# STUSB4500.net
KiCad netlist of a schematic drawn in EAGLE
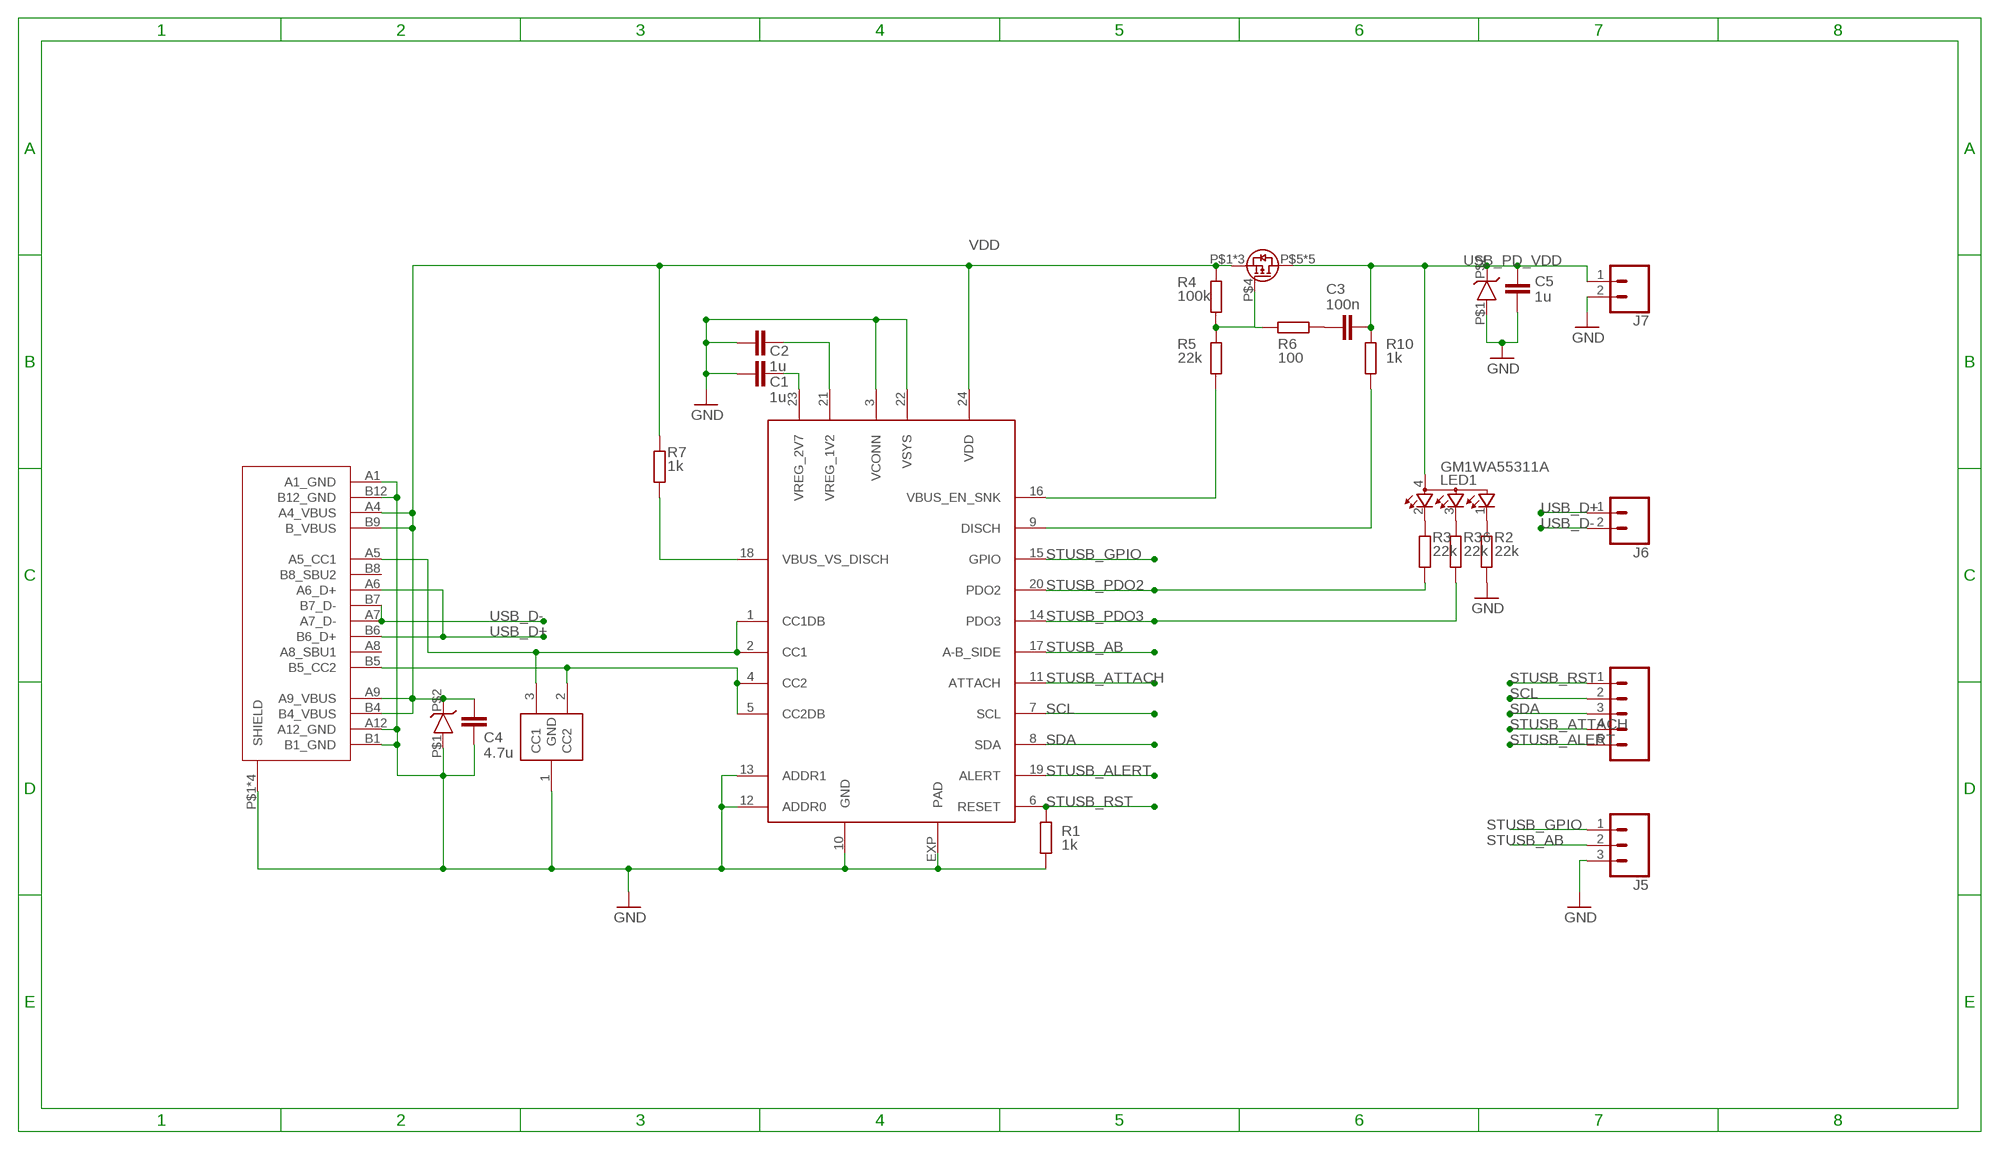
[diagram p0: schematic, sheet 1]

(export (version "E")
  (design (tool "Eeschema 10.0.6"))
  (components
    (comp (ref "C1")
      (value "1u")
      (footprint "eagle-import:C0402")
      (libsource (lib "eagle-import") (part "C-EUC0402"))
    )
    (comp (ref "C2")
      (value "1u")
      (footprint "eagle-import:C0402")
      (libsource (lib "eagle-import") (part "C-EUC0402"))
    )
    (comp (ref "C3")
      (value "100n")
      (footprint "eagle-import:C0402")
      (libsource (lib "eagle-import") (part "C-EUC0402"))
    )
    (comp (ref "C4")
      (value "4.7u")
      (footprint "eagle-import:C1206")
      (libsource (lib "eagle-import") (part "C-EUC1206"))
    )
    (comp (ref "C5")
      (value "1u")
      (footprint "eagle-import:C1206")
      (libsource (lib "eagle-import") (part "C-EUC1206"))
    )
    (comp (ref "ESDA25W")
      (value "ESDA25WSOT323")
      (footprint "eagle-import:SOT323")
      (libsource (lib "eagle-import") (part "ESDA25WSOT323"))
    )
    (comp (ref "J5")
      (value "CONN_031.27")
      (footprint "eagle-import:1X03_1.27MM")
      (libsource (lib "eagle-import") (part "CONN_031.27"))
    )
    (comp (ref "J6")
      (value "CONN_021.27")
      (footprint "eagle-import:1X02_1.27MM")
      (libsource (lib "eagle-import") (part "CONN_021.27"))
    )
    (comp (ref "J7")
      (value "CONN_02LOCK")
      (footprint "eagle-import:1X02_LOCK")
      (libsource (lib "eagle-import") (part "CONN_02LOCK"))
    )
    (comp (ref "J8")
      (value "CONN_051.27MM")
      (footprint "eagle-import:1X05_1.27MM")
      (libsource (lib "eagle-import") (part "CONN_051.27MM"))
    )
    (comp (ref "LED1")
      (value "GM1WA55311A")
      (footprint "eagle-import:GM1WA55311A")
      (libsource (lib "eagle-import") (part "GM1WA55311A"))
    )
    (comp (ref "R1")
      (value "1k")
      (footprint "eagle-import:R0402")
      (libsource (lib "eagle-import") (part "R-EU_R0402"))
    )
    (comp (ref "R2")
      (value "22k")
      (footprint "eagle-import:R0402")
      (libsource (lib "eagle-import") (part "R-EU_R0402"))
    )
    (comp (ref "R3")
      (value "22k")
      (footprint "eagle-import:R0402")
      (libsource (lib "eagle-import") (part "R-EU_R0402"))
    )
    (comp (ref "R4")
      (value "100k")
      (footprint "eagle-import:R0402")
      (libsource (lib "eagle-import") (part "R-EU_R0402"))
    )
    (comp (ref "R5")
      (value "22k")
      (footprint "eagle-import:R0402")
      (libsource (lib "eagle-import") (part "R-EU_R0402"))
    )
    (comp (ref "R6")
      (value "100")
      (footprint "eagle-import:R0402")
      (libsource (lib "eagle-import") (part "R-EU_R0402"))
    )
    (comp (ref "R7")
      (value "1k")
      (footprint "eagle-import:R0402")
      (libsource (lib "eagle-import") (part "R-EU_R0402"))
    )
    (comp (ref "R10")
      (value "1k")
      (footprint "eagle-import:R0402")
      (libsource (lib "eagle-import") (part "R-EU_R0402"))
    )
    (comp (ref "R36")
      (value "22k")
      (footprint "eagle-import:R0402")
      (libsource (lib "eagle-import") (part "R-EU_R0402"))
    )
    (comp (ref "U$1")
      (value "STUSB4500QFN24_4X4")
      (footprint "eagle-import:QFN24-4X4")
      (libsource (lib "eagle-import") (part "STUSB4500QFN24_4X4"))
    )
    (comp (ref "U$2")
      (value "USB-C")
      (footprint "eagle-import:USB-C_16P")
      (libsource (lib "eagle-import") (part "USB-C"))
    )
    (comp (ref "U$4")
      (value "ESDA25P35")
      (footprint "eagle-import:1610")
      (libsource (lib "eagle-import") (part "ESDA25P35"))
    )
    (comp (ref "U$5")
      (value "ESDA25P35")
      (footprint "eagle-import:1610")
      (libsource (lib "eagle-import") (part "ESDA25P35"))
    )
    (comp (ref "U$6")
      (value "STL6P3LLH6")
      (footprint "eagle-import:POWER_FLAT_3X3")
      (libsource (lib "eagle-import") (part "STL6P3LLH6"))
    )
  )
  (nets
    (net (code "1") (name "/SCL") (class "Default")
      (node (ref "J8") (pin "2") (pinfunction "2_2") (pintype "passive"))
      (node (ref "U$1") (pin "7") (pinfunction "SCL_7") (pintype "bidirectional"))
    )
    (net (code "2") (name "/SDA") (class "Default")
      (node (ref "J8") (pin "3") (pinfunction "3_3") (pintype "passive"))
      (node (ref "U$1") (pin "8") (pinfunction "SDA_8") (pintype "bidirectional"))
    )
    (net (code "3") (name "/STUSB_AB") (class "Default")
      (node (ref "J5") (pin "2") (pinfunction "2_2") (pintype "passive"))
      (node (ref "U$1") (pin "17") (pinfunction "A-B_SIDE_17") (pintype "bidirectional"))
    )
    (net (code "4") (name "/STUSB_ALERT") (class "Default")
      (node (ref "J8") (pin "5") (pinfunction "5_5") (pintype "passive"))
      (node (ref "U$1") (pin "19") (pinfunction "ALERT_19") (pintype "bidirectional"))
    )
    (net (code "5") (name "/STUSB_ATTACH") (class "Default")
      (node (ref "J8") (pin "4") (pinfunction "4_4") (pintype "passive"))
      (node (ref "U$1") (pin "11") (pinfunction "ATTACH_11") (pintype "bidirectional"))
    )
    (net (code "6") (name "/STUSB_GPIO") (class "Default")
      (node (ref "J5") (pin "1") (pinfunction "1_1") (pintype "passive"))
      (node (ref "U$1") (pin "15") (pinfunction "GPIO_15") (pintype "bidirectional"))
    )
    (net (code "7") (name "/STUSB_PDO2") (class "Default")
      (node (ref "R3") (pin "1") (pinfunction "1_1") (pintype "passive"))
      (node (ref "U$1") (pin "20") (pinfunction "PDO2_20") (pintype "bidirectional"))
    )
    (net (code "8") (name "/STUSB_PDO3") (class "Default")
      (node (ref "R36") (pin "1") (pinfunction "1_1") (pintype "passive"))
      (node (ref "U$1") (pin "14") (pinfunction "PDO3_14") (pintype "bidirectional"))
    )
    (net (code "9") (name "/STUSB_RST") (class "Default")
      (node (ref "J8") (pin "1") (pinfunction "1_1") (pintype "passive"))
      (node (ref "R1") (pin "2") (pinfunction "2_2") (pintype "passive"))
      (node (ref "U$1") (pin "6") (pinfunction "RESET_6") (pintype "bidirectional"))
    )
    (net (code "10") (name "/USB_D+") (class "Default")
      (node (ref "J6") (pin "1") (pinfunction "1_1") (pintype "passive"))
      (node (ref "U$2") (pin "A6") (pinfunction "A6_D+_A6") (pintype "bidirectional"))
      (node (ref "U$2") (pin "B6") (pinfunction "B6_D+_B6") (pintype "bidirectional"))
    )
    (net (code "11") (name "/USB_D-") (class "Default")
      (node (ref "J6") (pin "2") (pinfunction "2_2") (pintype "passive"))
      (node (ref "U$2") (pin "A7") (pinfunction "A7_D-_A7") (pintype "bidirectional"))
      (node (ref "U$2") (pin "B7") (pinfunction "B7_D-_B7") (pintype "bidirectional"))
    )
    (net (code "12") (name "/USB_PD_VDD") (class "Default")
      (node (ref "C3") (pin "2") (pinfunction "2_2") (pintype "passive"))
      (node (ref "C5") (pin "1") (pinfunction "1_1") (pintype "passive"))
      (node (ref "J7") (pin "1") (pinfunction "1_1") (pintype "passive"))
      (node (ref "LED1") (pin "4") (pinfunction "A_4") (pintype "passive"))
      (node (ref "R10") (pin "1") (pinfunction "1_1") (pintype "passive"))
      (node (ref "U$5") (pin "P$2") (pinfunction "VBUS_P$2") (pintype "bidirectional"))
      (node (ref "U$6") (pin "P$5") (pinfunction "D_P$5") (pintype "bidirectional"))
      (node (ref "U$6") (pin "P$6") (pinfunction "D_P$6") (pintype "bidirectional"))
      (node (ref "U$6") (pin "P$7") (pinfunction "D_P$7") (pintype "bidirectional"))
      (node (ref "U$6") (pin "P$8") (pinfunction "D_P$8") (pintype "bidirectional"))
      (node (ref "U$6") (pin "P$9") (pinfunction "D_P$9") (pintype "bidirectional"))
    )
    (net (code "13") (name "/VDD") (class "Default")
      (node (ref "C4") (pin "1") (pinfunction "1_1") (pintype "passive"))
      (node (ref "R4") (pin "2") (pinfunction "2_2") (pintype "passive"))
      (node (ref "R7") (pin "1") (pinfunction "1_1") (pintype "passive"))
      (node (ref "U$1") (pin "24") (pinfunction "VDD_24") (pintype "bidirectional"))
      (node (ref "U$2") (pin "A4") (pinfunction "A4_VBUS_A4") (pintype "bidirectional"))
      (node (ref "U$2") (pin "A9") (pinfunction "A9_VBUS_A9") (pintype "bidirectional"))
      (node (ref "U$2") (pin "B4") (pinfunction "B4_VBUS_B4") (pintype "bidirectional"))
      (node (ref "U$2") (pin "B9") (pinfunction "B_VBUS_B9") (pintype "bidirectional"))
      (node (ref "U$4") (pin "P$2") (pinfunction "VBUS_P$2") (pintype "bidirectional"))
      (node (ref "U$6") (pin "P$1") (pinfunction "S_P$1") (pintype "bidirectional"))
      (node (ref "U$6") (pin "P$2") (pinfunction "S_P$2") (pintype "bidirectional"))
      (node (ref "U$6") (pin "P$3") (pinfunction "S_P$3") (pintype "bidirectional"))
    )
    (net (code "14") (name "GND") (class "Default")
      (node (ref "C1") (pin "2") (pinfunction "2_2") (pintype "passive"))
      (node (ref "C2") (pin "2") (pinfunction "2_2") (pintype "passive"))
      (node (ref "C4") (pin "2") (pinfunction "2_2") (pintype "passive"))
      (node (ref "C5") (pin "2") (pinfunction "2_2") (pintype "passive"))
      (node (ref "ESDA25W") (pin "1") (pinfunction "GND_1") (pintype "bidirectional"))
      (node (ref "J5") (pin "3") (pinfunction "3_3") (pintype "passive"))
      (node (ref "J7") (pin "2") (pinfunction "2_2") (pintype "passive"))
      (node (ref "R1") (pin "1") (pinfunction "1_1") (pintype "passive"))
      (node (ref "R2") (pin "1") (pinfunction "1_1") (pintype "passive"))
      (node (ref "U$1") (pin "10") (pinfunction "GND_10") (pintype "bidirectional"))
      (node (ref "U$1") (pin "12") (pinfunction "ADDR0_12") (pintype "bidirectional"))
      (node (ref "U$1") (pin "13") (pinfunction "ADDR1_13") (pintype "bidirectional"))
      (node (ref "U$1") (pin "22") (pinfunction "VSYS_22") (pintype "bidirectional"))
      (node (ref "U$1") (pin "3") (pinfunction "VCONN_3") (pintype "bidirectional"))
      (node (ref "U$1") (pin "EXP") (pinfunction "PAD_EXP") (pintype "bidirectional"))
      (node (ref "U$2") (pin "A1") (pinfunction "A1_GND_A1") (pintype "bidirectional"))
      (node (ref "U$2") (pin "A12") (pinfunction "A12_GND_A12") (pintype "bidirectional"))
      (node (ref "U$2") (pin "B1") (pinfunction "B1_GND_B1") (pintype "bidirectional"))
      (node (ref "U$2") (pin "B12") (pinfunction "B12_GND_B12") (pintype "bidirectional"))
      (node (ref "U$2") (pin "P$1") (pinfunction "SHIELD_P$1") (pintype "bidirectional"))
      (node (ref "U$2") (pin "P$2") (pinfunction "SHIELD_P$2") (pintype "bidirectional"))
      (node (ref "U$2") (pin "P$3") (pinfunction "SHIELD_P$3") (pintype "bidirectional"))
      (node (ref "U$2") (pin "P$4") (pinfunction "SHIELD_P$4") (pintype "bidirectional"))
      (node (ref "U$4") (pin "P$1") (pinfunction "GND_P$1") (pintype "bidirectional"))
      (node (ref "U$5") (pin "P$1") (pinfunction "GND_P$1") (pintype "bidirectional"))
    )
    (net (code "15") (name "Net-(C3-Pad1)") (class "Default")
      (node (ref "C3") (pin "1") (pinfunction "1_1") (pintype "passive"))
      (node (ref "R6") (pin "1") (pinfunction "1_1") (pintype "passive"))
    )
    (net (code "16") (name "Net-(ESDA25W-CC1)") (class "Default")
      (node (ref "ESDA25W") (pin "3") (pinfunction "CC1_3") (pintype "bidirectional"))
      (node (ref "U$1") (pin "1") (pinfunction "CC1DB_1") (pintype "bidirectional"))
      (node (ref "U$1") (pin "2") (pinfunction "CC1_2") (pintype "bidirectional"))
      (node (ref "U$2") (pin "A5") (pinfunction "A5_CC1_A5") (pintype "bidirectional"))
    )
    (net (code "17") (name "Net-(ESDA25W-CC2)") (class "Default")
      (node (ref "ESDA25W") (pin "2") (pinfunction "CC2_2") (pintype "bidirectional"))
      (node (ref "U$1") (pin "4") (pinfunction "CC2_4") (pintype "bidirectional"))
      (node (ref "U$1") (pin "5") (pinfunction "CC2DB_5") (pintype "bidirectional"))
      (node (ref "U$2") (pin "B5") (pinfunction "B5_CC2_B5") (pintype "bidirectional"))
    )
    (net (code "18") (name "Net-(LED1-CBLUE)") (class "Default")
      (node (ref "LED1") (pin "3") (pinfunction "CBLUE_3") (pintype "passive"))
      (node (ref "R36") (pin "2") (pinfunction "2_2") (pintype "passive"))
    )
    (net (code "19") (name "Net-(LED1-CGREEN)") (class "Default")
      (node (ref "LED1") (pin "1") (pinfunction "CGREEN_1") (pintype "passive"))
      (node (ref "R2") (pin "2") (pinfunction "2_2") (pintype "passive"))
    )
    (net (code "20") (name "Net-(LED1-CRED)") (class "Default")
      (node (ref "LED1") (pin "2") (pinfunction "CRED_2") (pintype "passive"))
      (node (ref "R3") (pin "2") (pinfunction "2_2") (pintype "passive"))
    )
    (net (code "21") (name "Net-(U$1-DISCH)") (class "Default")
      (node (ref "R10") (pin "2") (pinfunction "2_2") (pintype "passive"))
      (node (ref "U$1") (pin "9") (pinfunction "DISCH_9") (pintype "bidirectional"))
    )
    (net (code "22") (name "Net-(U$1-VBUS_EN_SNK)") (class "Default")
      (node (ref "R5") (pin "1") (pinfunction "1_1") (pintype "passive"))
      (node (ref "U$1") (pin "16") (pinfunction "VBUS_EN_SNK_16") (pintype "bidirectional"))
    )
    (net (code "23") (name "Net-(U$1-VBUS_VS_DISCH)") (class "Default")
      (node (ref "R7") (pin "2") (pinfunction "2_2") (pintype "passive"))
      (node (ref "U$1") (pin "18") (pinfunction "VBUS_VS_DISCH_18") (pintype "bidirectional"))
    )
    (net (code "24") (name "Net-(U$1-VREG_1V2)") (class "Default")
      (node (ref "C2") (pin "1") (pinfunction "1_1") (pintype "passive"))
      (node (ref "U$1") (pin "21") (pinfunction "VREG_1V2_21") (pintype "bidirectional"))
    )
    (net (code "25") (name "Net-(U$1-VREG_2V7)") (class "Default")
      (node (ref "C1") (pin "1") (pinfunction "1_1") (pintype "passive"))
      (node (ref "U$1") (pin "23") (pinfunction "VREG_2V7_23") (pintype "bidirectional"))
    )
    (net (code "26") (name "Net-(U$6-G)") (class "Default")
      (node (ref "R4") (pin "1") (pinfunction "1_1") (pintype "passive"))
      (node (ref "R5") (pin "2") (pinfunction "2_2") (pintype "passive"))
      (node (ref "R6") (pin "2") (pinfunction "2_2") (pintype "passive"))
      (node (ref "U$6") (pin "P$4") (pinfunction "G_P$4") (pintype "bidirectional"))
    )
    (net (code "27") (name "unconnected-(U$2-A8_SBU1-PadA8)") (class "Default")
      (node (ref "U$2") (pin "A8") (pinfunction "A8_SBU1_A8") (pintype "bidirectional"))
    )
    (net (code "28") (name "unconnected-(U$2-B8_SBU2-PadB8)") (class "Default")
      (node (ref "U$2") (pin "B8") (pinfunction "B8_SBU2_B8") (pintype "bidirectional"))
    )
  )
)
